# OptoInputs.net
KiCad netlist of a schematic drawn in EAGLE
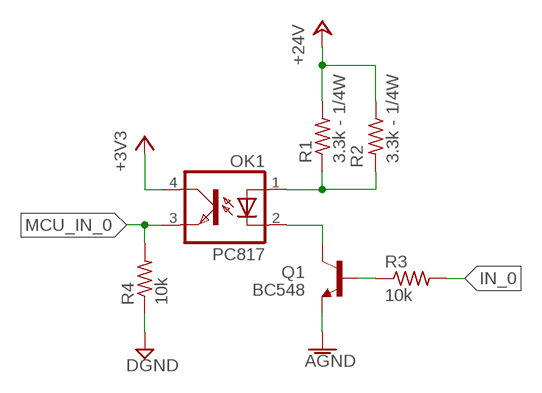
[diagram p0: schematic, sheet 1]

(export (version "E")
  (design (tool "Eeschema 10.0.6"))
  (components
    (comp (ref "OK1")
      (value "PC817")
      (footprint "eagle-import:DIL04")
      (fields (field (name "MPN") "PC817X4J000F"))
      (libsource (lib "eagle-import") (part "PC817"))
    )
    (comp (ref "Q1")
      (value "BC548")
      (footprint "eagle-import:TO92-EBC")
      (libsource (lib "eagle-import") (part "BC548"))
    )
    (comp (ref "R1")
      (value "3.3k - 1/4W")
      (footprint "eagle-import:0204V")
      (libsource (lib "eagle-import") (part "R-US_0204/2V"))
    )
    (comp (ref "R2")
      (value "3.3k - 1/4W")
      (footprint "eagle-import:0204V")
      (libsource (lib "eagle-import") (part "R-US_0204/2V"))
    )
    (comp (ref "R3")
      (value "10k")
      (footprint "eagle-import:0204_5")
      (libsource (lib "eagle-import") (part "R-US_0204/5"))
    )
    (comp (ref "R4")
      (value "10k")
      (footprint "eagle-import:R0402")
      (libsource (lib "eagle-import") (part "R-US_R0402"))
    )
  )
  (nets
    (net (code "1") (name "+3V3") (class "Default")
      (node (ref "OK1") (pin "4") (pinfunction "COL_4") (pintype "passive"))
    )
    (net (code "2") (name "+24V") (class "Default")
      (node (ref "R1") (pin "2") (pinfunction "2_2") (pintype "passive"))
      (node (ref "R2") (pin "1") (pinfunction "1_1") (pintype "passive"))
    )
    (net (code "3") (name "AGND") (class "Default")
      (node (ref "Q1") (pin "E") (pinfunction "E_E") (pintype "passive"))
    )
    (net (code "4") (name "DGND") (class "Default")
      (node (ref "R4") (pin "1") (pinfunction "1_1") (pintype "passive"))
    )
    (net (code "5") (name "IN_0") (class "Default")
      (node (ref "R3") (pin "2") (pinfunction "2_2") (pintype "passive"))
    )
    (net (code "6") (name "MCU_IN_0") (class "Default")
      (node (ref "OK1") (pin "3") (pinfunction "EMIT_3") (pintype "passive"))
      (node (ref "R4") (pin "2") (pinfunction "2_2") (pintype "passive"))
    )
    (net (code "7") (name "Net-(OK1-A)") (class "Default")
      (node (ref "OK1") (pin "1") (pinfunction "A_1") (pintype "passive"))
      (node (ref "R1") (pin "1") (pinfunction "1_1") (pintype "passive"))
      (node (ref "R2") (pin "2") (pinfunction "2_2") (pintype "passive"))
    )
    (net (code "8") (name "Net-(OK1-C)") (class "Default")
      (node (ref "OK1") (pin "2") (pinfunction "C_2") (pintype "passive"))
      (node (ref "Q1") (pin "C") (pinfunction "C_C") (pintype "passive"))
    )
    (net (code "9") (name "Net-(Q1-PadB)") (class "Default")
      (node (ref "Q1") (pin "B") (pinfunction "B_B") (pintype "passive"))
      (node (ref "R3") (pin "1") (pinfunction "1_1") (pintype "passive"))
    )
  )
)
